# single_chebyshev.net
KiCad netlist of a schematic drawn in Altium Designer
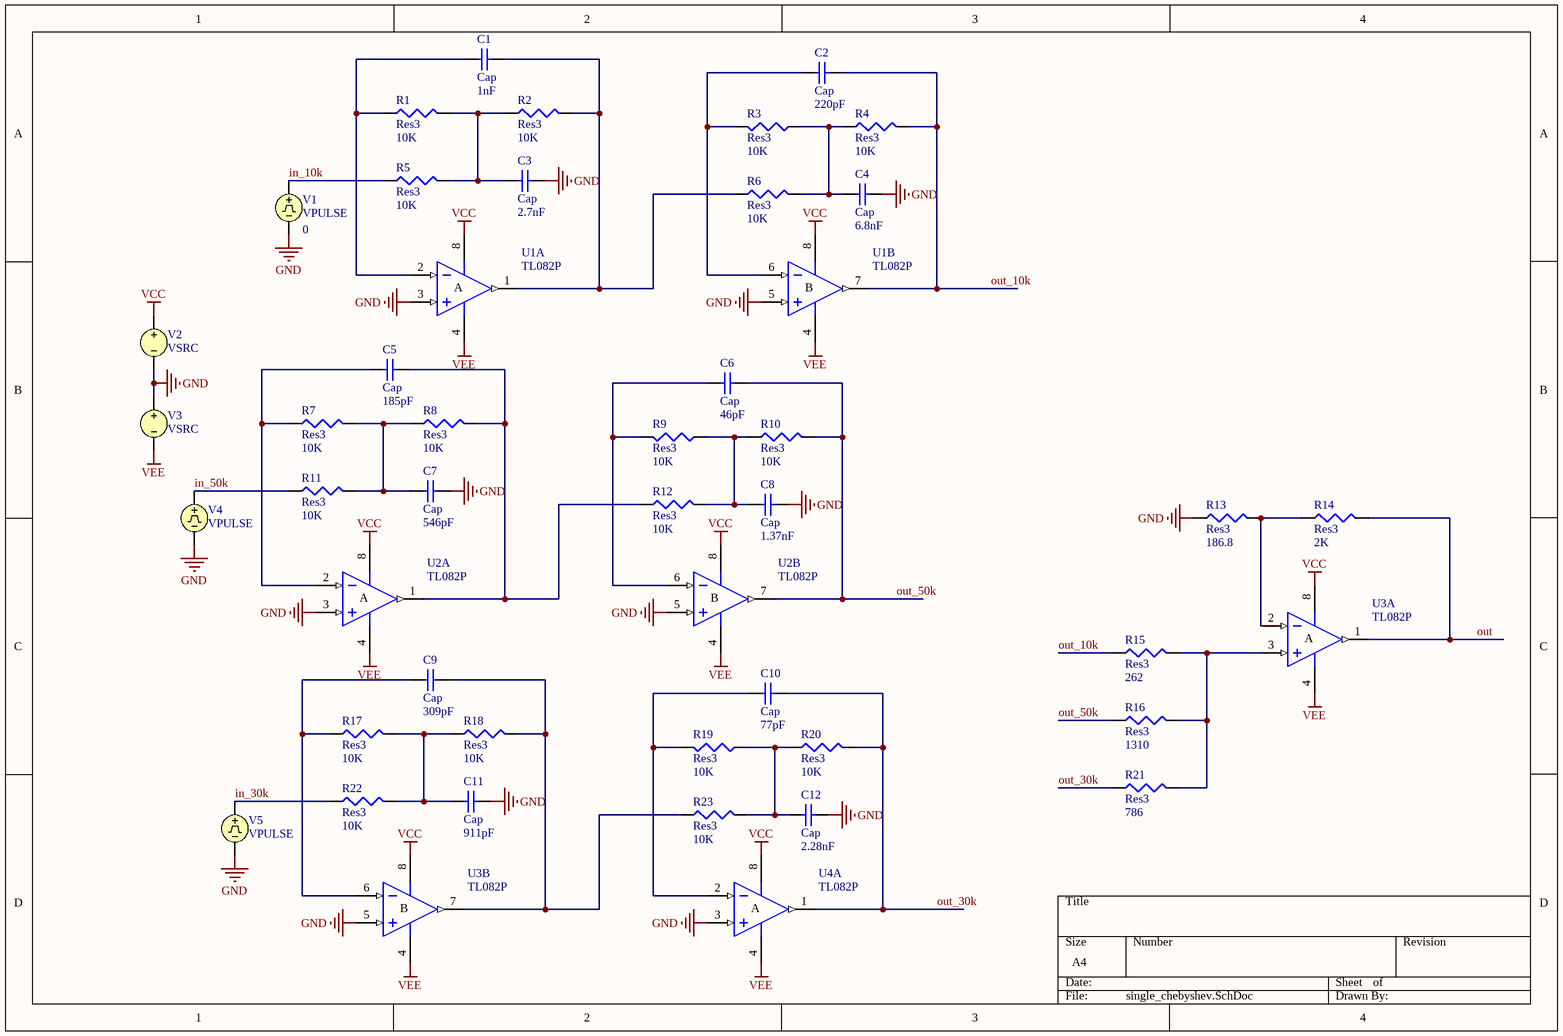
[diagram p0: single_chebyshev.SchDoc]

(export (version "E")
  (design (tool "Eeschema 10.0.6"))
  (components
    (comp (ref "C1")
      (value "Cap")
      (footprint "RAD-0.3")
      (description "Capacitor")
      (fields (field (name "ALTIUM_VALUE") "1nF") (field (name "PUBLISHER") "Altium Limited"))
      (libsource (lib "Miscellaneous Devices") (part "Cap"))
    )
    (comp (ref "C2")
      (value "Cap")
      (footprint "RAD-0.3")
      (description "Capacitor")
      (fields (field (name "ALTIUM_VALUE") "220pF") (field (name "PUBLISHER") "Altium Limited"))
      (libsource (lib "Miscellaneous Devices") (part "Cap"))
    )
    (comp (ref "C3")
      (value "Cap")
      (footprint "RAD-0.3")
      (description "Capacitor")
      (fields (field (name "ALTIUM_VALUE") "2.7nF") (field (name "PUBLISHER") "Altium Limited"))
      (libsource (lib "Miscellaneous Devices") (part "Cap"))
    )
    (comp (ref "C4")
      (value "Cap")
      (footprint "RAD-0.3")
      (description "Capacitor")
      (fields (field (name "ALTIUM_VALUE") "6.8nF") (field (name "PUBLISHER") "Altium Limited"))
      (libsource (lib "Miscellaneous Devices") (part "Cap"))
    )
    (comp (ref "C5")
      (value "Cap")
      (footprint "RAD-0.3")
      (description "Capacitor")
      (fields (field (name "ALTIUM_VALUE") "185pF") (field (name "PUBLISHER") "Altium Limited"))
      (libsource (lib "Miscellaneous Devices") (part "Cap"))
    )
    (comp (ref "C6")
      (value "Cap")
      (footprint "RAD-0.3")
      (description "Capacitor")
      (fields (field (name "ALTIUM_VALUE") "46pF") (field (name "PUBLISHER") "Altium Limited"))
      (libsource (lib "Miscellaneous Devices") (part "Cap"))
    )
    (comp (ref "C7")
      (value "Cap")
      (footprint "RAD-0.3")
      (description "Capacitor")
      (fields (field (name "ALTIUM_VALUE") "546pF") (field (name "PUBLISHER") "Altium Limited"))
      (libsource (lib "Miscellaneous Devices") (part "Cap"))
    )
    (comp (ref "C8")
      (value "Cap")
      (footprint "RAD-0.3")
      (description "Capacitor")
      (fields (field (name "ALTIUM_VALUE") "1.37nF") (field (name "PUBLISHER") "Altium Limited"))
      (libsource (lib "Miscellaneous Devices") (part "Cap"))
    )
    (comp (ref "C9")
      (value "Cap")
      (footprint "RAD-0.3")
      (description "Capacitor")
      (fields (field (name "ALTIUM_VALUE") "309pF") (field (name "PUBLISHER") "Altium Limited"))
      (libsource (lib "Miscellaneous Devices") (part "Cap"))
    )
    (comp (ref "C10")
      (value "Cap")
      (footprint "RAD-0.3")
      (description "Capacitor")
      (fields (field (name "ALTIUM_VALUE") "77pF") (field (name "PUBLISHER") "Altium Limited"))
      (libsource (lib "Miscellaneous Devices") (part "Cap"))
    )
    (comp (ref "C11")
      (value "Cap")
      (footprint "RAD-0.3")
      (description "Capacitor")
      (fields (field (name "ALTIUM_VALUE") "911pF") (field (name "PUBLISHER") "Altium Limited"))
      (libsource (lib "Miscellaneous Devices") (part "Cap"))
    )
    (comp (ref "C12")
      (value "Cap")
      (footprint "RAD-0.3")
      (description "Capacitor")
      (fields (field (name "ALTIUM_VALUE") "2.28nF") (field (name "PUBLISHER") "Altium Limited"))
      (libsource (lib "Miscellaneous Devices") (part "Cap"))
    )
    (comp (ref "R1")
      (value "Res3")
      (footprint "J1-0603")
      (description "Resistor")
      (fields (field (name "ALTIUM_VALUE") "10K") (field (name "PUBLISHER") "Altium Limited"))
      (libsource (lib "Miscellaneous Devices") (part "Res3"))
    )
    (comp (ref "R2")
      (value "Res3")
      (footprint "J1-0603")
      (description "Resistor")
      (fields (field (name "ALTIUM_VALUE") "10K") (field (name "PUBLISHER") "Altium Limited"))
      (libsource (lib "Miscellaneous Devices") (part "Res3"))
    )
    (comp (ref "R3")
      (value "Res3")
      (footprint "J1-0603")
      (description "Resistor")
      (fields (field (name "ALTIUM_VALUE") "10K") (field (name "PUBLISHER") "Altium Limited"))
      (libsource (lib "Miscellaneous Devices") (part "Res3"))
    )
    (comp (ref "R4")
      (value "Res3")
      (footprint "J1-0603")
      (description "Resistor")
      (fields (field (name "ALTIUM_VALUE") "10K") (field (name "PUBLISHER") "Altium Limited"))
      (libsource (lib "Miscellaneous Devices") (part "Res3"))
    )
    (comp (ref "R5")
      (value "Res3")
      (footprint "J1-0603")
      (description "Resistor")
      (fields (field (name "ALTIUM_VALUE") "10K") (field (name "PUBLISHER") "Altium Limited"))
      (libsource (lib "Miscellaneous Devices") (part "Res3"))
    )
    (comp (ref "R6")
      (value "Res3")
      (footprint "J1-0603")
      (description "Resistor")
      (fields (field (name "ALTIUM_VALUE") "10K") (field (name "PUBLISHER") "Altium Limited"))
      (libsource (lib "Miscellaneous Devices") (part "Res3"))
    )
    (comp (ref "R7")
      (value "Res3")
      (footprint "J1-0603")
      (description "Resistor")
      (fields (field (name "ALTIUM_VALUE") "10K") (field (name "PUBLISHER") "Altium Limited"))
      (libsource (lib "Miscellaneous Devices") (part "Res3"))
    )
    (comp (ref "R8")
      (value "Res3")
      (footprint "J1-0603")
      (description "Resistor")
      (fields (field (name "ALTIUM_VALUE") "10K") (field (name "PUBLISHER") "Altium Limited"))
      (libsource (lib "Miscellaneous Devices") (part "Res3"))
    )
    (comp (ref "R9")
      (value "Res3")
      (footprint "J1-0603")
      (description "Resistor")
      (fields (field (name "ALTIUM_VALUE") "10K") (field (name "PUBLISHER") "Altium Limited"))
      (libsource (lib "Miscellaneous Devices") (part "Res3"))
    )
    (comp (ref "R10")
      (value "Res3")
      (footprint "J1-0603")
      (description "Resistor")
      (fields (field (name "ALTIUM_VALUE") "10K") (field (name "PUBLISHER") "Altium Limited"))
      (libsource (lib "Miscellaneous Devices") (part "Res3"))
    )
    (comp (ref "R11")
      (value "Res3")
      (footprint "J1-0603")
      (description "Resistor")
      (fields (field (name "ALTIUM_VALUE") "10K") (field (name "PUBLISHER") "Altium Limited"))
      (libsource (lib "Miscellaneous Devices") (part "Res3"))
    )
    (comp (ref "R12")
      (value "Res3")
      (footprint "J1-0603")
      (description "Resistor")
      (fields (field (name "ALTIUM_VALUE") "10K") (field (name "PUBLISHER") "Altium Limited"))
      (libsource (lib "Miscellaneous Devices") (part "Res3"))
    )
    (comp (ref "R13")
      (value "Res3")
      (footprint "J1-0603")
      (description "Resistor")
      (fields (field (name "ALTIUM_VALUE") "186.8") (field (name "PUBLISHER") "Altium Limited"))
      (libsource (lib "Miscellaneous Devices") (part "Res3"))
    )
    (comp (ref "R14")
      (value "Res3")
      (footprint "J1-0603")
      (description "Resistor")
      (fields (field (name "ALTIUM_VALUE") "2K") (field (name "PUBLISHER") "Altium Limited"))
      (libsource (lib "Miscellaneous Devices") (part "Res3"))
    )
    (comp (ref "R15")
      (value "Res3")
      (footprint "J1-0603")
      (description "Resistor")
      (fields (field (name "ALTIUM_VALUE") "262") (field (name "PUBLISHER") "Altium Limited"))
      (libsource (lib "Miscellaneous Devices") (part "Res3"))
    )
    (comp (ref "R16")
      (value "Res3")
      (footprint "J1-0603")
      (description "Resistor")
      (fields (field (name "ALTIUM_VALUE") "1310") (field (name "PUBLISHER") "Altium Limited"))
      (libsource (lib "Miscellaneous Devices") (part "Res3"))
    )
    (comp (ref "R17")
      (value "Res3")
      (footprint "J1-0603")
      (description "Resistor")
      (fields (field (name "ALTIUM_VALUE") "10K") (field (name "PUBLISHER") "Altium Limited"))
      (libsource (lib "Miscellaneous Devices") (part "Res3"))
    )
    (comp (ref "R18")
      (value "Res3")
      (footprint "J1-0603")
      (description "Resistor")
      (fields (field (name "ALTIUM_VALUE") "10K") (field (name "PUBLISHER") "Altium Limited"))
      (libsource (lib "Miscellaneous Devices") (part "Res3"))
    )
    (comp (ref "R19")
      (value "Res3")
      (footprint "J1-0603")
      (description "Resistor")
      (fields (field (name "ALTIUM_VALUE") "10K") (field (name "PUBLISHER") "Altium Limited"))
      (libsource (lib "Miscellaneous Devices") (part "Res3"))
    )
    (comp (ref "R20")
      (value "Res3")
      (footprint "J1-0603")
      (description "Resistor")
      (fields (field (name "ALTIUM_VALUE") "10K") (field (name "PUBLISHER") "Altium Limited"))
      (libsource (lib "Miscellaneous Devices") (part "Res3"))
    )
    (comp (ref "R21")
      (value "Res3")
      (footprint "J1-0603")
      (description "Resistor")
      (fields (field (name "ALTIUM_VALUE") "786") (field (name "PUBLISHER") "Altium Limited"))
      (libsource (lib "Miscellaneous Devices") (part "Res3"))
    )
    (comp (ref "R22")
      (value "Res3")
      (footprint "J1-0603")
      (description "Resistor")
      (fields (field (name "ALTIUM_VALUE") "10K") (field (name "PUBLISHER") "Altium Limited"))
      (libsource (lib "Miscellaneous Devices") (part "Res3"))
    )
    (comp (ref "R23")
      (value "Res3")
      (footprint "J1-0603")
      (description "Resistor")
      (fields (field (name "ALTIUM_VALUE") "10K") (field (name "PUBLISHER") "Altium Limited"))
      (libsource (lib "Miscellaneous Devices") (part "Res3"))
    )
    (comp (ref "U1")
      (value "TL082P")
      (footprint "P008")
      (description "JFET-Input Operational Amplifier")
      (fields (field (name "PUBLISHER") "Altium Limited"))
      (libsource (lib "TI Operational Amplifier") (part "TL082P"))
    )
    (comp (ref "U2")
      (value "TL082P")
      (footprint "P008")
      (description "JFET-Input Operational Amplifier")
      (fields (field (name "PUBLISHER") "Altium Limited"))
      (libsource (lib "TI Operational Amplifier") (part "TL082P"))
    )
    (comp (ref "U3")
      (value "TL082P")
      (footprint "P008")
      (description "JFET-Input Operational Amplifier")
      (fields (field (name "PUBLISHER") "Altium Limited"))
      (libsource (lib "TI Operational Amplifier") (part "TL082P"))
    )
    (comp (ref "U4")
      (value "TL082P")
      (footprint "P008")
      (description "JFET-Input Operational Amplifier")
      (fields (field (name "PUBLISHER") "Altium Limited"))
      (libsource (lib "TI Operational Amplifier") (part "TL082P"))
    )
    (comp (ref "V1")
      (value "VPULSE")
      (description "Pulse Voltage Source")
      (fields (field (name "AC PHASE") "0") (field (name "PUBLISHER") "Altium Limited"))
      (libsource (lib "Simulation Sources") (part "VPULSE"))
    )
    (comp (ref "V2")
      (value "VSRC")
      (description "Voltage Source")
      (fields (field (name "PUBLISHER") "Altium Limited"))
      (libsource (lib "Simulation Sources") (part "VSRC"))
    )
    (comp (ref "V3")
      (value "VSRC")
      (description "Voltage Source")
      (fields (field (name "PUBLISHER") "Altium Limited"))
      (libsource (lib "Simulation Sources") (part "VSRC"))
    )
    (comp (ref "V4")
      (value "VPULSE")
      (description "Pulse Voltage Source")
      (fields (field (name "PUBLISHER") "Altium Limited"))
      (libsource (lib "Simulation Sources") (part "VPULSE"))
    )
    (comp (ref "V5")
      (value "VPULSE")
      (description "Pulse Voltage Source")
      (fields (field (name "PUBLISHER") "Altium Limited"))
      (libsource (lib "Simulation Sources") (part "VPULSE"))
    )
  )
  (nets
    (net (code "1") (name "/in_10k") (class "Default")
      (node (ref "R5") (pin "1") (pinfunction "1_1") (pintype "passive"))
      (node (ref "V1") (pin "1") (pinfunction "1_1") (pintype "passive"))
    )
    (net (code "2") (name "/in_30k") (class "Default")
      (node (ref "R22") (pin "1") (pinfunction "1_1") (pintype "passive"))
      (node (ref "V5") (pin "1") (pinfunction "1_1") (pintype "passive"))
    )
    (net (code "3") (name "/in_50k") (class "Default")
      (node (ref "R11") (pin "1") (pinfunction "1_1") (pintype "passive"))
      (node (ref "V4") (pin "1") (pinfunction "1_1") (pintype "passive"))
    )
    (net (code "4") (name "/out") (class "Default")
      (node (ref "R14") (pin "2") (pinfunction "2_2") (pintype "passive"))
      (node (ref "U3") (pin "1") (pinfunction "OUT_1") (pintype "output"))
    )
    (net (code "5") (name "/out_10k") (class "Default")
      (node (ref "C2") (pin "2") (pinfunction "2_2") (pintype "passive"))
      (node (ref "R15") (pin "1") (pinfunction "1_1") (pintype "passive"))
      (node (ref "R4") (pin "2") (pinfunction "2_2") (pintype "passive"))
      (node (ref "U1") (pin "7") (pinfunction "OUT_7") (pintype "output"))
    )
    (net (code "6") (name "/out_30k") (class "Default")
      (node (ref "C10") (pin "2") (pinfunction "2_2") (pintype "passive"))
      (node (ref "R20") (pin "2") (pinfunction "2_2") (pintype "passive"))
      (node (ref "R21") (pin "1") (pinfunction "1_1") (pintype "passive"))
      (node (ref "U4") (pin "1") (pinfunction "OUT_1") (pintype "output"))
    )
    (net (code "7") (name "/out_50k") (class "Default")
      (node (ref "C6") (pin "2") (pinfunction "2_2") (pintype "passive"))
      (node (ref "R10") (pin "2") (pinfunction "2_2") (pintype "passive"))
      (node (ref "R16") (pin "1") (pinfunction "1_1") (pintype "passive"))
      (node (ref "U2") (pin "7") (pinfunction "OUT_7") (pintype "output"))
    )
    (net (code "8") (name "GND") (class "Default")
      (node (ref "C11") (pin "2") (pinfunction "2_2") (pintype "passive"))
      (node (ref "C12") (pin "2") (pinfunction "2_2") (pintype "passive"))
      (node (ref "C3") (pin "2") (pinfunction "2_2") (pintype "passive"))
      (node (ref "C4") (pin "2") (pinfunction "2_2") (pintype "passive"))
      (node (ref "C7") (pin "2") (pinfunction "2_2") (pintype "passive"))
      (node (ref "C8") (pin "2") (pinfunction "2_2") (pintype "passive"))
      (node (ref "R13") (pin "1") (pinfunction "1_1") (pintype "passive"))
      (node (ref "U1") (pin "3") (pinfunction "IN+_3") (pintype "input"))
      (node (ref "U1") (pin "5") (pinfunction "IN+_5") (pintype "input"))
      (node (ref "U2") (pin "3") (pinfunction "IN+_3") (pintype "input"))
      (node (ref "U2") (pin "5") (pinfunction "IN+_5") (pintype "input"))
      (node (ref "U3") (pin "5") (pinfunction "IN+_5") (pintype "input"))
      (node (ref "U4") (pin "3") (pinfunction "IN+_3") (pintype "input"))
      (node (ref "V1") (pin "2") (pinfunction "2_2") (pintype "passive"))
      (node (ref "V2") (pin "2") (pinfunction "2_2") (pintype "passive"))
      (node (ref "V3") (pin "1") (pinfunction "1_1") (pintype "passive"))
      (node (ref "V4") (pin "2") (pinfunction "2_2") (pintype "passive"))
      (node (ref "V5") (pin "2") (pinfunction "2_2") (pintype "passive"))
    )
    (net (code "9") (name "Net-(C3-Pad1)") (class "Default")
      (node (ref "C3") (pin "1") (pinfunction "1_1") (pintype "passive"))
      (node (ref "R1") (pin "2") (pinfunction "2_2") (pintype "passive"))
      (node (ref "R2") (pin "1") (pinfunction "1_1") (pintype "passive"))
      (node (ref "R5") (pin "2") (pinfunction "2_2") (pintype "passive"))
    )
    (net (code "10") (name "Net-(C4-Pad1)") (class "Default")
      (node (ref "C4") (pin "1") (pinfunction "1_1") (pintype "passive"))
      (node (ref "R3") (pin "1") (pinfunction "1_1") (pintype "passive"))
      (node (ref "R4") (pin "1") (pinfunction "1_1") (pintype "passive"))
      (node (ref "R6") (pin "2") (pinfunction "2_2") (pintype "passive"))
    )
    (net (code "11") (name "Net-(C7-Pad1)") (class "Default")
      (node (ref "C7") (pin "1") (pinfunction "1_1") (pintype "passive"))
      (node (ref "R11") (pin "2") (pinfunction "2_2") (pintype "passive"))
      (node (ref "R7") (pin "2") (pinfunction "2_2") (pintype "passive"))
      (node (ref "R8") (pin "1") (pinfunction "1_1") (pintype "passive"))
    )
    (net (code "12") (name "Net-(C8-Pad1)") (class "Default")
      (node (ref "C8") (pin "1") (pinfunction "1_1") (pintype "passive"))
      (node (ref "R10") (pin "1") (pinfunction "1_1") (pintype "passive"))
      (node (ref "R12") (pin "2") (pinfunction "2_2") (pintype "passive"))
      (node (ref "R9") (pin "1") (pinfunction "1_1") (pintype "passive"))
    )
    (net (code "13") (name "Net-(C11-Pad1)") (class "Default")
      (node (ref "C11") (pin "1") (pinfunction "1_1") (pintype "passive"))
      (node (ref "R17") (pin "2") (pinfunction "2_2") (pintype "passive"))
      (node (ref "R18") (pin "1") (pinfunction "1_1") (pintype "passive"))
      (node (ref "R22") (pin "2") (pinfunction "2_2") (pintype "passive"))
    )
    (net (code "14") (name "Net-(C12-Pad1)") (class "Default")
      (node (ref "C12") (pin "1") (pinfunction "1_1") (pintype "passive"))
      (node (ref "R19") (pin "1") (pinfunction "1_1") (pintype "passive"))
      (node (ref "R20") (pin "1") (pinfunction "1_1") (pintype "passive"))
      (node (ref "R23") (pin "2") (pinfunction "2_2") (pintype "passive"))
    )
    (net (code "15") (name "Net-(U1A-IN-)") (class "Default")
      (node (ref "C1") (pin "1") (pinfunction "1_1") (pintype "passive"))
      (node (ref "R1") (pin "1") (pinfunction "1_1") (pintype "passive"))
      (node (ref "U1") (pin "2") (pinfunction "IN-_2") (pintype "input"))
    )
    (net (code "16") (name "Net-(U1A-OUT)") (class "Default")
      (node (ref "C1") (pin "2") (pinfunction "2_2") (pintype "passive"))
      (node (ref "R2") (pin "2") (pinfunction "2_2") (pintype "passive"))
      (node (ref "R6") (pin "1") (pinfunction "1_1") (pintype "passive"))
      (node (ref "U1") (pin "1") (pinfunction "OUT_1") (pintype "output"))
    )
    (net (code "17") (name "Net-(U1B-IN-)") (class "Default")
      (node (ref "C2") (pin "1") (pinfunction "1_1") (pintype "passive"))
      (node (ref "R3") (pin "2") (pinfunction "2_2") (pintype "passive"))
      (node (ref "U1") (pin "6") (pinfunction "IN-_6") (pintype "input"))
    )
    (net (code "18") (name "Net-(U2A-IN-)") (class "Default")
      (node (ref "C5") (pin "1") (pinfunction "1_1") (pintype "passive"))
      (node (ref "R7") (pin "1") (pinfunction "1_1") (pintype "passive"))
      (node (ref "U2") (pin "2") (pinfunction "IN-_2") (pintype "input"))
    )
    (net (code "19") (name "Net-(U2A-OUT)") (class "Default")
      (node (ref "C5") (pin "2") (pinfunction "2_2") (pintype "passive"))
      (node (ref "R12") (pin "1") (pinfunction "1_1") (pintype "passive"))
      (node (ref "R8") (pin "2") (pinfunction "2_2") (pintype "passive"))
      (node (ref "U2") (pin "1") (pinfunction "OUT_1") (pintype "output"))
    )
    (net (code "20") (name "Net-(U2B-IN-)") (class "Default")
      (node (ref "C6") (pin "1") (pinfunction "1_1") (pintype "passive"))
      (node (ref "R9") (pin "2") (pinfunction "2_2") (pintype "passive"))
      (node (ref "U2") (pin "6") (pinfunction "IN-_6") (pintype "input"))
    )
    (net (code "21") (name "Net-(U3A-IN+)") (class "Default")
      (node (ref "R15") (pin "2") (pinfunction "2_2") (pintype "passive"))
      (node (ref "R16") (pin "2") (pinfunction "2_2") (pintype "passive"))
      (node (ref "R21") (pin "2") (pinfunction "2_2") (pintype "passive"))
      (node (ref "U3") (pin "3") (pinfunction "IN+_3") (pintype "input"))
    )
    (net (code "22") (name "Net-(U3A-IN-)") (class "Default")
      (node (ref "R13") (pin "2") (pinfunction "2_2") (pintype "passive"))
      (node (ref "R14") (pin "1") (pinfunction "1_1") (pintype "passive"))
      (node (ref "U3") (pin "2") (pinfunction "IN-_2") (pintype "input"))
    )
    (net (code "23") (name "Net-(U3B-IN-)") (class "Default")
      (node (ref "C9") (pin "1") (pinfunction "1_1") (pintype "passive"))
      (node (ref "R17") (pin "1") (pinfunction "1_1") (pintype "passive"))
      (node (ref "U3") (pin "6") (pinfunction "IN-_6") (pintype "input"))
    )
    (net (code "24") (name "Net-(U3B-OUT)") (class "Default")
      (node (ref "C9") (pin "2") (pinfunction "2_2") (pintype "passive"))
      (node (ref "R18") (pin "2") (pinfunction "2_2") (pintype "passive"))
      (node (ref "R23") (pin "1") (pinfunction "1_1") (pintype "passive"))
      (node (ref "U3") (pin "7") (pinfunction "OUT_7") (pintype "output"))
    )
    (net (code "25") (name "Net-(U4A-IN-)") (class "Default")
      (node (ref "C10") (pin "1") (pinfunction "1_1") (pintype "passive"))
      (node (ref "R19") (pin "2") (pinfunction "2_2") (pintype "passive"))
      (node (ref "U4") (pin "2") (pinfunction "IN-_2") (pintype "input"))
    )
    (net (code "26") (name "VCC") (class "Default")
      (node (ref "U1") (pin "8") (pinfunction "V+_8") (pintype "power_in"))
      (node (ref "U2") (pin "8") (pinfunction "V+_8") (pintype "power_in"))
      (node (ref "U3") (pin "8") (pinfunction "V+_8") (pintype "power_in"))
      (node (ref "U4") (pin "8") (pinfunction "V+_8") (pintype "power_in"))
      (node (ref "V2") (pin "1") (pinfunction "1_1") (pintype "passive"))
    )
    (net (code "27") (name "VEE") (class "Default")
      (node (ref "U1") (pin "4") (pinfunction "V-_4") (pintype "power_in"))
      (node (ref "U2") (pin "4") (pinfunction "V-_4") (pintype "power_in"))
      (node (ref "U3") (pin "4") (pinfunction "V-_4") (pintype "power_in"))
      (node (ref "U4") (pin "4") (pinfunction "V-_4") (pintype "power_in"))
      (node (ref "V3") (pin "2") (pinfunction "2_2") (pintype "passive"))
    )
  )
)
